# chapr.net
KiCad netlist of a schematic drawn in EAGLE
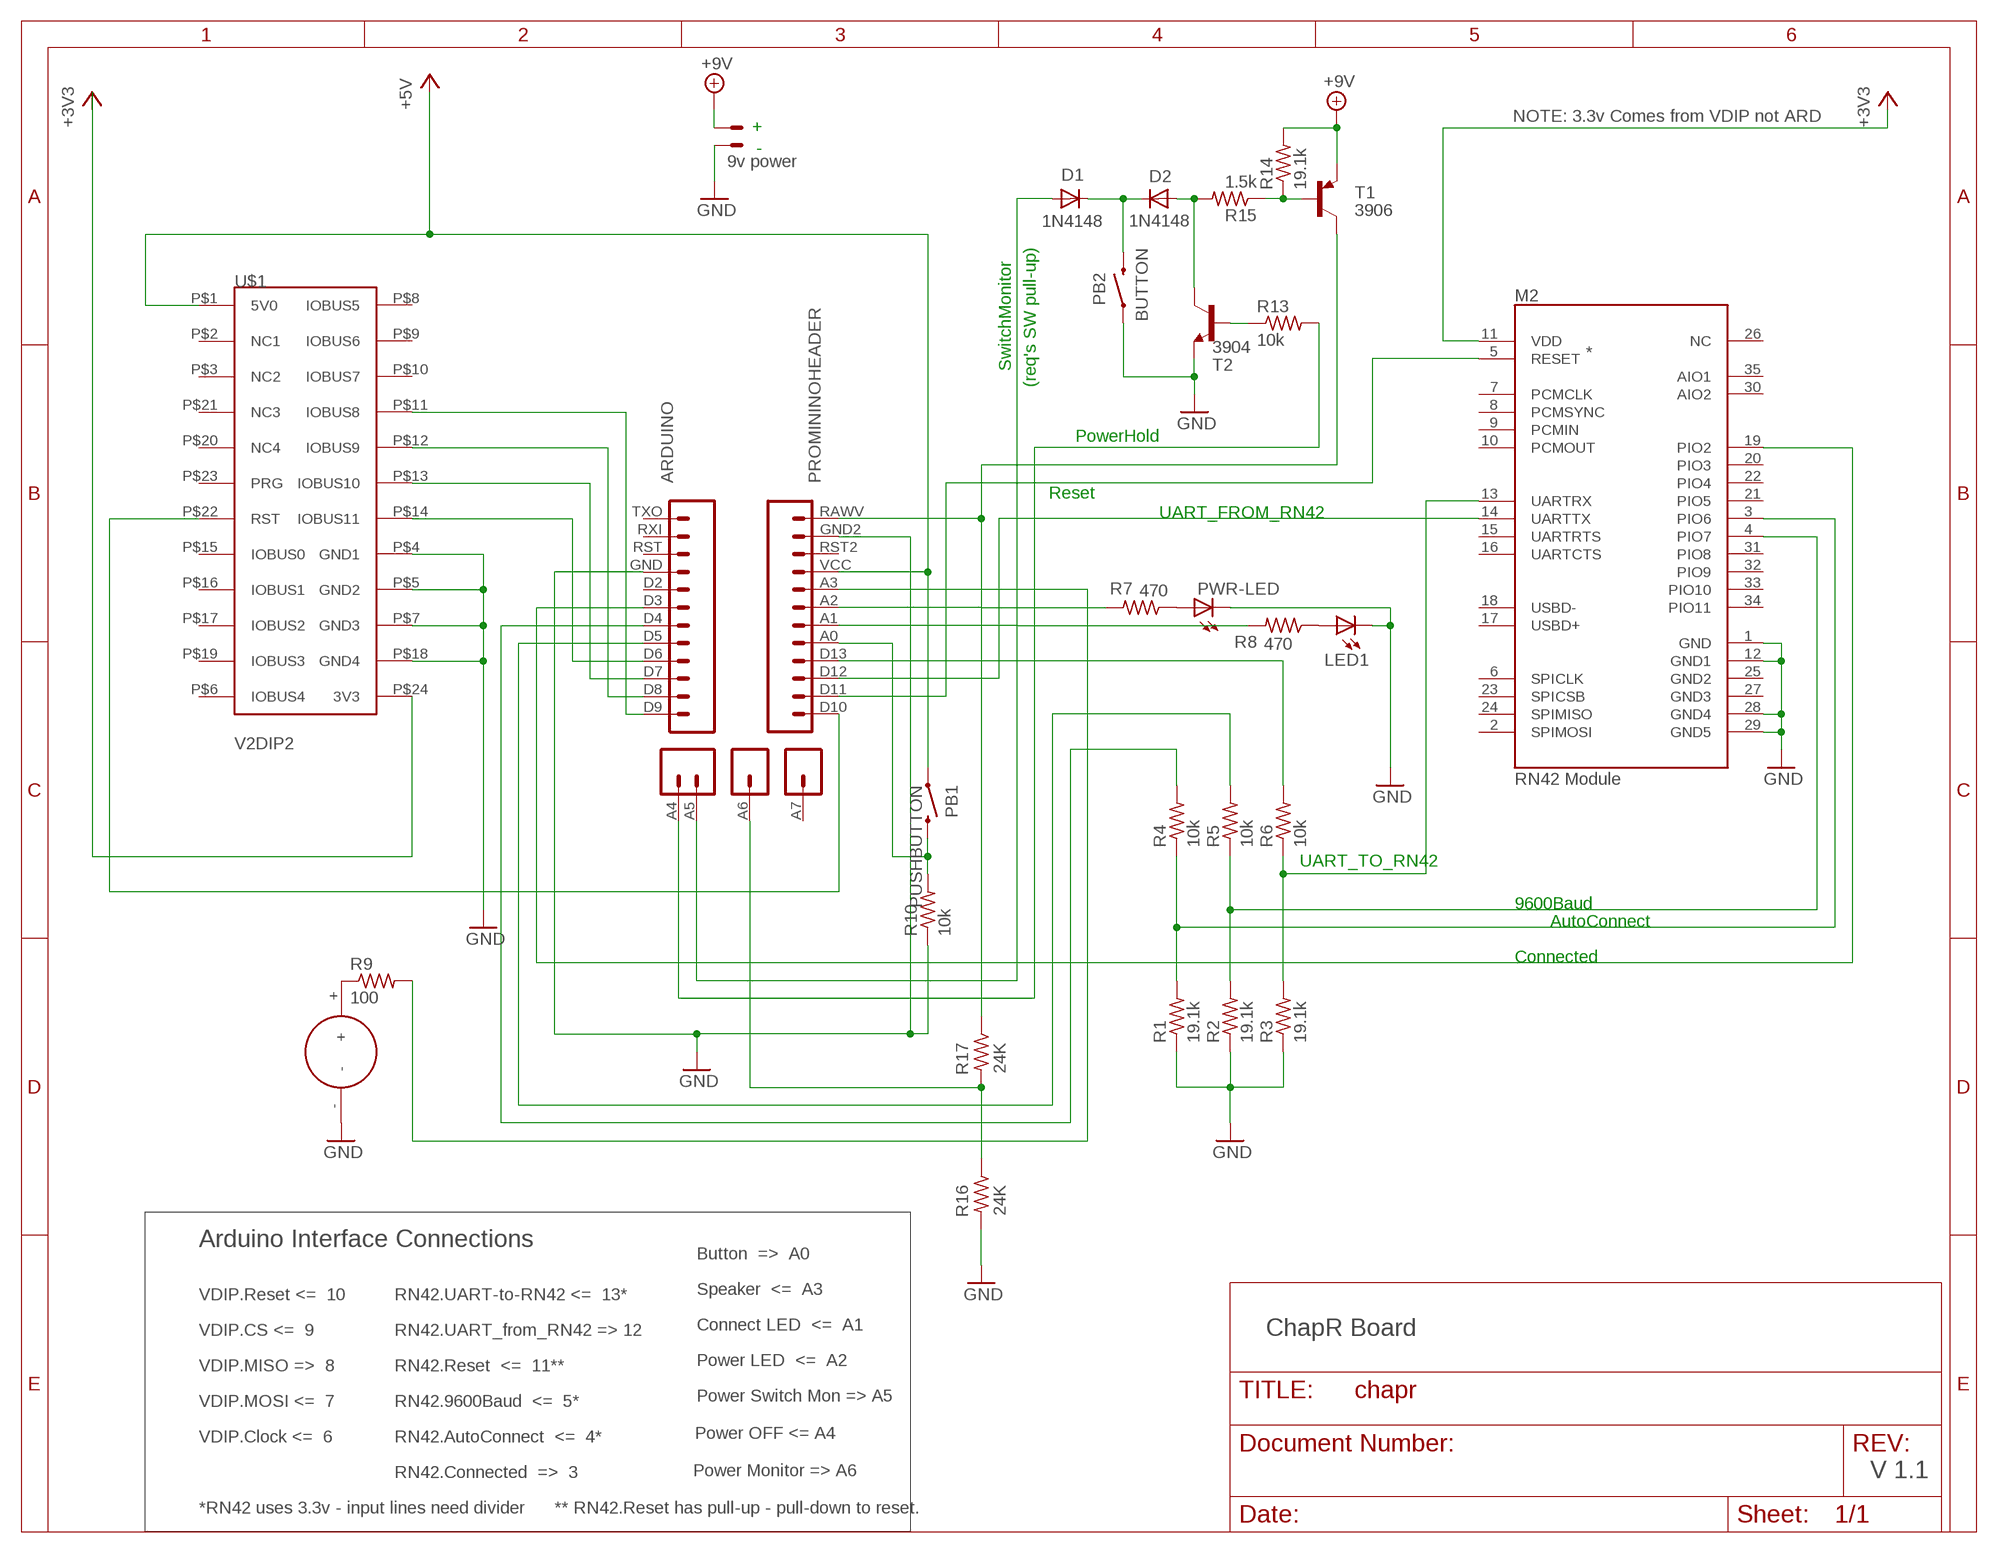
[diagram p0: schematic, sheet 1]

(export (version "E")
  (design (tool "Eeschema 10.0.6"))
  (components
    (comp (ref "-")
      (value "9v power")
      (footprint "eagle-import:22-23-2021")
      (fields (field (name "MF") "MOLEX") (field (name "MPN") "22-23-2021"))
      (libsource (lib "eagle-import") (part "22-23-2021"))
    )
    (comp (ref "ARDUINO")
      (value "PROMININOHEADER")
      (footprint "eagle-import:PROMININOHEADER")
      (libsource (lib "eagle-import") (part "PROMININOHEADER"))
    )
    (comp (ref "D1")
      (value "1N4148")
      (footprint "eagle-import:DO35-7")
      (libsource (lib "eagle-import") (part "1N4148DO35-7"))
    )
    (comp (ref "D2")
      (value "1N4148")
      (footprint "eagle-import:DO35-7")
      (libsource (lib "eagle-import") (part "1N4148DO35-7"))
    )
    (comp (ref "LED1")
      (value "LED3MM")
      (footprint "eagle-import:LED3MM")
      (libsource (lib "eagle-import") (part "LED3MM"))
    )
    (comp (ref "M2")
      (value "RN42 Module")
      (footprint "eagle-import:RN41")
      (libsource (lib "eagle-import") (part "BLUETOOTH-RN41{dblquote}"))
    )
    (comp (ref "PB1")
      (value "PUSHBUTTON")
      (footprint "eagle-import:2-PIN-PUSHBUTTON")
      (libsource (lib "eagle-import") (part "PUSHBUTTON"))
    )
    (comp (ref "PB2")
      (value "BUTTON")
      (footprint "eagle-import:2-PIN-PUSHBUTTON")
      (libsource (lib "eagle-import") (part "PUSHBUTTON"))
    )
    (comp (ref "PWR-LED")
      (value "LED3MM")
      (footprint "eagle-import:LED3MM")
      (libsource (lib "eagle-import") (part "LED3MM"))
    )
    (comp (ref "R1")
      (value "19.1k")
      (footprint "eagle-import:0207_10")
      (libsource (lib "eagle-import") (part "R-US_0207/10"))
    )
    (comp (ref "R2")
      (value "19.1k")
      (footprint "eagle-import:0207_10")
      (libsource (lib "eagle-import") (part "R-US_0207/10"))
    )
    (comp (ref "R3")
      (value "19.1k")
      (footprint "eagle-import:0207_10")
      (libsource (lib "eagle-import") (part "R-US_0207/10"))
    )
    (comp (ref "R4")
      (value "10k")
      (footprint "eagle-import:0207_10")
      (libsource (lib "eagle-import") (part "R-US_0207/10"))
    )
    (comp (ref "R5")
      (value "10k")
      (footprint "eagle-import:0207_10")
      (libsource (lib "eagle-import") (part "R-US_0207/10"))
    )
    (comp (ref "R6")
      (value "10k")
      (footprint "eagle-import:0207_10")
      (libsource (lib "eagle-import") (part "R-US_0207/10"))
    )
    (comp (ref "R7")
      (value "470")
      (footprint "eagle-import:0207_10")
      (libsource (lib "eagle-import") (part "R-US_0207/10"))
    )
    (comp (ref "R8")
      (value "470")
      (footprint "eagle-import:0207_10")
      (libsource (lib "eagle-import") (part "R-US_0207/10"))
    )
    (comp (ref "R9")
      (value "100")
      (footprint "eagle-import:0207_10")
      (libsource (lib "eagle-import") (part "R-US_0207/10"))
    )
    (comp (ref "R10")
      (value "10k")
      (footprint "eagle-import:0207_10")
      (libsource (lib "eagle-import") (part "R-US_0207/10"))
    )
    (comp (ref "R13")
      (value "10k")
      (footprint "eagle-import:0207_10")
      (libsource (lib "eagle-import") (part "R-US_0207/10"))
    )
    (comp (ref "R14")
      (value "19.1k")
      (footprint "eagle-import:0207_10")
      (libsource (lib "eagle-import") (part "R-US_0207/10"))
    )
    (comp (ref "R15")
      (value "1.5k")
      (footprint "eagle-import:0207_10")
      (libsource (lib "eagle-import") (part "R-US_0207/10"))
    )
    (comp (ref "R16")
      (value "24K")
      (footprint "eagle-import:0207_10")
      (libsource (lib "eagle-import") (part "R-US_0207/10"))
    )
    (comp (ref "R17")
      (value "24K")
      (footprint "eagle-import:0207_10")
      (libsource (lib "eagle-import") (part "R-US_0207/10"))
    )
    (comp (ref "T1")
      (value "3906")
      (footprint "eagle-import:TO92-EBC")
      (libsource (lib "eagle-import") (part "-PNP-TO92-EBC"))
    )
    (comp (ref "T2")
      (value "3904")
      (footprint "eagle-import:TO92-EBC")
      (libsource (lib "eagle-import") (part "-NPN-TO92-EBC"))
    )
    (comp (ref "U$1")
      (value "V2DIP2")
      (footprint "eagle-import:V2DIP2")
      (libsource (lib "eagle-import") (part "V2DIP2"))
    )
    (comp (ref "U$2")
      (value "SPEAKER")
      (footprint "eagle-import:SPEAKER")
      (libsource (lib "eagle-import") (part "SPEAKER"))
    )
  )
  (nets
    (net (code "1") (name "+3V3") (class "Default")
      (node (ref "M2") (pin "11") (pinfunction "VDD_11") (pintype "bidirectional"))
      (node (ref "U$1") (pin "P$24") (pinfunction "3V3_P$24") (pintype "bidirectional"))
    )
    (net (code "2") (name "+5V") (class "Default")
      (node (ref "ARDUINO") (pin "VCC") (pinfunction "VCC_VCC") (pintype "passive"))
      (node (ref "PB1") (pin "P$1") (pinfunction "1_P$1") (pintype "passive"))
      (node (ref "U$1") (pin "P$1") (pinfunction "5V0_P$1") (pintype "bidirectional"))
    )
    (net (code "3") (name "+9V") (class "Default")
      (node (ref "-") (pin "2") (pinfunction "S_2") (pintype "passive"))
      (node (ref "R14") (pin "2") (pinfunction "2_2") (pintype "passive"))
      (node (ref "T1") (pin "E") (pinfunction "E_E") (pintype "passive"))
    )
    (net (code "4") (name "GND") (class "Default")
      (node (ref "-") (pin "1") (pinfunction "S_1") (pintype "passive"))
      (node (ref "ARDUINO") (pin "GND") (pinfunction "GND_GND") (pintype "passive"))
      (node (ref "ARDUINO") (pin "GND2") (pinfunction "GND2_GND2") (pintype "passive"))
      (node (ref "LED1") (pin "K") (pinfunction "C_K") (pintype "passive"))
      (node (ref "M2") (pin "1") (pinfunction "GND_1") (pintype "bidirectional"))
      (node (ref "M2") (pin "12") (pinfunction "GND1_12") (pintype "bidirectional"))
      (node (ref "M2") (pin "28") (pinfunction "GND4_28") (pintype "bidirectional"))
      (node (ref "M2") (pin "29") (pinfunction "GND5_29") (pintype "bidirectional"))
      (node (ref "PB2") (pin "P$1") (pinfunction "1_P$1") (pintype "passive"))
      (node (ref "PWR-LED") (pin "K") (pinfunction "C_K") (pintype "passive"))
      (node (ref "R1") (pin "1") (pinfunction "1_1") (pintype "passive"))
      (node (ref "R10") (pin "1") (pinfunction "1_1") (pintype "passive"))
      (node (ref "R16") (pin "2") (pinfunction "2_2") (pintype "passive"))
      (node (ref "R2") (pin "1") (pinfunction "1_1") (pintype "passive"))
      (node (ref "R3") (pin "1") (pinfunction "1_1") (pintype "passive"))
      (node (ref "T2") (pin "E") (pinfunction "E_E") (pintype "passive"))
      (node (ref "U$1") (pin "P$18") (pinfunction "GND4_P$18") (pintype "bidirectional"))
      (node (ref "U$1") (pin "P$4") (pinfunction "GND1_P$4") (pintype "bidirectional"))
      (node (ref "U$1") (pin "P$5") (pinfunction "GND2_P$5") (pintype "bidirectional"))
      (node (ref "U$1") (pin "P$7") (pinfunction "GND3_P$7") (pintype "bidirectional"))
      (node (ref "U$2") (pin "-") (pinfunction "-_-") (pintype "bidirectional"))
    )
    (net (code "5") (name "Net-(ARDUINO-PadA1)") (class "Default")
      (node (ref "ARDUINO") (pin "A1") (pinfunction "A1_A1") (pintype "passive"))
      (node (ref "R8") (pin "2") (pinfunction "2_2") (pintype "passive"))
    )
    (net (code "6") (name "Net-(ARDUINO-PadA2)") (class "Default")
      (node (ref "ARDUINO") (pin "A2") (pinfunction "A2_A2") (pintype "passive"))
      (node (ref "R7") (pin "2") (pinfunction "2_2") (pintype "passive"))
    )
    (net (code "7") (name "Net-(ARDUINO-PadA3)") (class "Default")
      (node (ref "ARDUINO") (pin "A3") (pinfunction "A3_A3") (pintype "passive"))
      (node (ref "R9") (pin "2") (pinfunction "2_2") (pintype "passive"))
    )
    (net (code "8") (name "Net-(ARDUINO-PadA4)") (class "Default")
      (node (ref "ARDUINO") (pin "A4") (pinfunction "A4_A4") (pintype "passive"))
      (node (ref "R13") (pin "2") (pinfunction "2_2") (pintype "passive"))
    )
    (net (code "9") (name "Net-(ARDUINO-PadA5)") (class "Default")
      (node (ref "ARDUINO") (pin "A5") (pinfunction "A5_A5") (pintype "passive"))
      (node (ref "D1") (pin "A") (pinfunction "A_A") (pintype "passive"))
    )
    (net (code "10") (name "Net-(ARDUINO-PadA6)") (class "Default")
      (node (ref "ARDUINO") (pin "A6") (pinfunction "A6_A6") (pintype "passive"))
      (node (ref "R16") (pin "1") (pinfunction "1_1") (pintype "passive"))
      (node (ref "R17") (pin "2") (pinfunction "2_2") (pintype "passive"))
    )
    (net (code "11") (name "Net-(ARDUINO-PadD4)") (class "Default")
      (node (ref "ARDUINO") (pin "D4") (pinfunction "D4_D4") (pintype "passive"))
      (node (ref "R4") (pin "2") (pinfunction "2_2") (pintype "passive"))
    )
    (net (code "12") (name "Net-(ARDUINO-PadD5)") (class "Default")
      (node (ref "ARDUINO") (pin "D5") (pinfunction "D5_D5") (pintype "passive"))
      (node (ref "R5") (pin "2") (pinfunction "2_2") (pintype "passive"))
    )
    (net (code "13") (name "Net-(ARDUINO-PadD13)") (class "Default")
      (node (ref "ARDUINO") (pin "D13") (pinfunction "D13_D13") (pintype "passive"))
      (node (ref "R6") (pin "2") (pinfunction "2_2") (pintype "passive"))
    )
    (net (code "14") (name "Net-(ARDUINO-PadRAWV)") (class "Default")
      (node (ref "ARDUINO") (pin "RAWV") (pinfunction "RAWV_RAWV") (pintype "passive"))
      (node (ref "R17") (pin "1") (pinfunction "1_1") (pintype "passive"))
      (node (ref "T1") (pin "C") (pinfunction "C_C") (pintype "passive"))
    )
    (net (code "15") (name "Net-(D2-PadA)") (class "Default")
      (node (ref "D2") (pin "A") (pinfunction "A_A") (pintype "passive"))
      (node (ref "R15") (pin "2") (pinfunction "2_2") (pintype "passive"))
      (node (ref "T2") (pin "C") (pinfunction "C_C") (pintype "passive"))
    )
    (net (code "16") (name "Net-(LED1-PadA)") (class "Default")
      (node (ref "LED1") (pin "A") (pinfunction "A_A") (pintype "passive"))
      (node (ref "R8") (pin "1") (pinfunction "1_1") (pintype "passive"))
    )
    (net (code "17") (name "Net-(M2-PIO2)") (class "Default")
      (node (ref "ARDUINO") (pin "D3") (pinfunction "D3_D3") (pintype "passive"))
      (node (ref "M2") (pin "19") (pinfunction "PIO2_19") (pintype "bidirectional"))
    )
    (net (code "18") (name "Net-(M2-PIO6)") (class "Default")
      (node (ref "M2") (pin "3") (pinfunction "PIO6_3") (pintype "bidirectional"))
      (node (ref "R1") (pin "2") (pinfunction "2_2") (pintype "passive"))
      (node (ref "R4") (pin "1") (pinfunction "1_1") (pintype "passive"))
    )
    (net (code "19") (name "Net-(M2-PIO7)") (class "Default")
      (node (ref "M2") (pin "4") (pinfunction "PIO7_4") (pintype "bidirectional"))
      (node (ref "R2") (pin "2") (pinfunction "2_2") (pintype "passive"))
      (node (ref "R5") (pin "1") (pinfunction "1_1") (pintype "passive"))
    )
    (net (code "20") (name "Net-(M2-RESET)") (class "Default")
      (node (ref "ARDUINO") (pin "D11") (pinfunction "D11_D11") (pintype "passive"))
      (node (ref "M2") (pin "5") (pinfunction "RESET_5") (pintype "bidirectional"))
    )
    (net (code "21") (name "Net-(M2-UARTRX)") (class "Default")
      (node (ref "M2") (pin "13") (pinfunction "UARTRX_13") (pintype "bidirectional"))
      (node (ref "R3") (pin "2") (pinfunction "2_2") (pintype "passive"))
      (node (ref "R6") (pin "1") (pinfunction "1_1") (pintype "passive"))
    )
    (net (code "22") (name "Net-(M2-UARTTX)") (class "Default")
      (node (ref "ARDUINO") (pin "D12") (pinfunction "D12_D12") (pintype "passive"))
      (node (ref "M2") (pin "14") (pinfunction "UARTTX_14") (pintype "bidirectional"))
    )
    (net (code "23") (name "Net-(PB1-2)") (class "Default")
      (node (ref "ARDUINO") (pin "A0") (pinfunction "A0_A0") (pintype "passive"))
      (node (ref "PB1") (pin "P$2") (pinfunction "2_P$2") (pintype "passive"))
      (node (ref "R10") (pin "2") (pinfunction "2_2") (pintype "passive"))
    )
    (net (code "24") (name "Net-(PB2-2)") (class "Default")
      (node (ref "D1") (pin "C") (pinfunction "C_C") (pintype "passive"))
      (node (ref "D2") (pin "C") (pinfunction "C_C") (pintype "passive"))
      (node (ref "PB2") (pin "P$2") (pinfunction "2_P$2") (pintype "passive"))
    )
    (net (code "25") (name "Net-(PWR-LED-PadA)") (class "Default")
      (node (ref "PWR-LED") (pin "A") (pinfunction "A_A") (pintype "passive"))
      (node (ref "R7") (pin "1") (pinfunction "1_1") (pintype "passive"))
    )
    (net (code "26") (name "Net-(R9-Pad1)") (class "Default")
      (node (ref "R9") (pin "1") (pinfunction "1_1") (pintype "passive"))
      (node (ref "U$2") (pin "+") (pinfunction "+_+") (pintype "bidirectional"))
    )
    (net (code "27") (name "Net-(R13-Pad1)") (class "Default")
      (node (ref "R13") (pin "1") (pinfunction "1_1") (pintype "passive"))
      (node (ref "T2") (pin "B") (pinfunction "B_B") (pintype "passive"))
    )
    (net (code "28") (name "Net-(R14-Pad1)") (class "Default")
      (node (ref "R14") (pin "1") (pinfunction "1_1") (pintype "passive"))
      (node (ref "R15") (pin "1") (pinfunction "1_1") (pintype "passive"))
      (node (ref "T1") (pin "B") (pinfunction "B_B") (pintype "passive"))
    )
    (net (code "29") (name "Net-(U$1-IOBUS8)") (class "Default")
      (node (ref "ARDUINO") (pin "D9") (pinfunction "D9_D9") (pintype "passive"))
      (node (ref "U$1") (pin "P$11") (pinfunction "IOBUS8_P$11") (pintype "bidirectional"))
    )
    (net (code "30") (name "Net-(U$1-IOBUS9)") (class "Default")
      (node (ref "ARDUINO") (pin "D8") (pinfunction "D8_D8") (pintype "passive"))
      (node (ref "U$1") (pin "P$12") (pinfunction "IOBUS9_P$12") (pintype "bidirectional"))
    )
    (net (code "31") (name "Net-(U$1-IOBUS10)") (class "Default")
      (node (ref "ARDUINO") (pin "D7") (pinfunction "D7_D7") (pintype "passive"))
      (node (ref "U$1") (pin "P$13") (pinfunction "IOBUS10_P$13") (pintype "bidirectional"))
    )
    (net (code "32") (name "Net-(U$1-IOBUS11)") (class "Default")
      (node (ref "ARDUINO") (pin "D6") (pinfunction "D6_D6") (pintype "passive"))
      (node (ref "U$1") (pin "P$14") (pinfunction "IOBUS11_P$14") (pintype "bidirectional"))
    )
    (net (code "33") (name "Net-(U$1-RST)") (class "Default")
      (node (ref "ARDUINO") (pin "D10") (pinfunction "D10_D10") (pintype "passive"))
      (node (ref "U$1") (pin "P$22") (pinfunction "RST_P$22") (pintype "bidirectional"))
    )
    (net (code "34") (name "unconnected-(ARDUINO-PadA7)") (class "Default")
      (node (ref "ARDUINO") (pin "A7") (pinfunction "A7_A7") (pintype "passive"))
    )
    (net (code "35") (name "unconnected-(ARDUINO-PadD2)") (class "Default")
      (node (ref "ARDUINO") (pin "D2") (pinfunction "D2_D2") (pintype "passive"))
    )
    (net (code "36") (name "unconnected-(ARDUINO-PadRST)") (class "Default")
      (node (ref "ARDUINO") (pin "RST") (pinfunction "RST_RST") (pintype "passive"))
    )
    (net (code "37") (name "unconnected-(ARDUINO-PadRST2)") (class "Default")
      (node (ref "ARDUINO") (pin "RST2") (pinfunction "RST2_RST2") (pintype "passive"))
    )
    (net (code "38") (name "unconnected-(ARDUINO-PadRXI)") (class "Default")
      (node (ref "ARDUINO") (pin "RXI") (pinfunction "RXI_RXI") (pintype "passive"))
    )
    (net (code "39") (name "unconnected-(ARDUINO-PadTXO)") (class "Default")
      (node (ref "ARDUINO") (pin "TXO") (pinfunction "TXO_TXO") (pintype "passive"))
    )
    (net (code "40") (name "unconnected-(M2-AIO1-Pad35)") (class "Default")
      (node (ref "M2") (pin "35") (pinfunction "AIO1_35") (pintype "bidirectional"))
    )
    (net (code "41") (name "unconnected-(M2-AIO2-Pad30)") (class "Default")
      (node (ref "M2") (pin "30") (pinfunction "AIO2_30") (pintype "bidirectional"))
    )
    (net (code "42") (name "unconnected-(M2-GND2-Pad25)") (class "Default")
      (node (ref "M2") (pin "25") (pinfunction "GND2_25") (pintype "bidirectional"))
    )
    (net (code "43") (name "unconnected-(M2-GND3-Pad27)") (class "Default")
      (node (ref "M2") (pin "27") (pinfunction "GND3_27") (pintype "bidirectional"))
    )
    (net (code "44") (name "unconnected-(M2-NC-Pad26)") (class "Default")
      (node (ref "M2") (pin "26") (pinfunction "NC_26") (pintype "bidirectional"))
    )
    (net (code "45") (name "unconnected-(M2-PCMCLK-Pad7)") (class "Default")
      (node (ref "M2") (pin "7") (pinfunction "PCMCLK_7") (pintype "bidirectional"))
    )
    (net (code "46") (name "unconnected-(M2-PCMIN-Pad9)") (class "Default")
      (node (ref "M2") (pin "9") (pinfunction "PCMIN_9") (pintype "bidirectional"))
    )
    (net (code "47") (name "unconnected-(M2-PCMOUT-Pad10)") (class "Default")
      (node (ref "M2") (pin "10") (pinfunction "PCMOUT_10") (pintype "bidirectional"))
    )
    (net (code "48") (name "unconnected-(M2-PCMSYNC-Pad8)") (class "Default")
      (node (ref "M2") (pin "8") (pinfunction "PCMSYNC_8") (pintype "bidirectional"))
    )
    (net (code "49") (name "unconnected-(M2-PIO3-Pad20)") (class "Default")
      (node (ref "M2") (pin "20") (pinfunction "PIO3_20") (pintype "bidirectional"))
    )
    (net (code "50") (name "unconnected-(M2-PIO4-Pad22)") (class "Default")
      (node (ref "M2") (pin "22") (pinfunction "PIO4_22") (pintype "bidirectional"))
    )
    (net (code "51") (name "unconnected-(M2-PIO5-Pad21)") (class "Default")
      (node (ref "M2") (pin "21") (pinfunction "PIO5_21") (pintype "bidirectional"))
    )
    (net (code "52") (name "unconnected-(M2-PIO8-Pad31)") (class "Default")
      (node (ref "M2") (pin "31") (pinfunction "PIO8_31") (pintype "bidirectional"))
    )
    (net (code "53") (name "unconnected-(M2-PIO9-Pad32)") (class "Default")
      (node (ref "M2") (pin "32") (pinfunction "PIO9_32") (pintype "bidirectional"))
    )
    (net (code "54") (name "unconnected-(M2-PIO10-Pad33)") (class "Default")
      (node (ref "M2") (pin "33") (pinfunction "PIO10_33") (pintype "bidirectional"))
    )
    (net (code "55") (name "unconnected-(M2-PIO11-Pad34)") (class "Default")
      (node (ref "M2") (pin "34") (pinfunction "PIO11_34") (pintype "bidirectional"))
    )
    (net (code "56") (name "unconnected-(M2-SPICLK-Pad6)") (class "Default")
      (node (ref "M2") (pin "6") (pinfunction "SPICLK_6") (pintype "bidirectional"))
    )
    (net (code "57") (name "unconnected-(M2-SPICSB-Pad23)") (class "Default")
      (node (ref "M2") (pin "23") (pinfunction "SPICSB_23") (pintype "bidirectional"))
    )
    (net (code "58") (name "unconnected-(M2-SPIMISO-Pad24)") (class "Default")
      (node (ref "M2") (pin "24") (pinfunction "SPIMISO_24") (pintype "bidirectional"))
    )
    (net (code "59") (name "unconnected-(M2-SPIMOSI-Pad2)") (class "Default")
      (node (ref "M2") (pin "2") (pinfunction "SPIMOSI_2") (pintype "bidirectional"))
    )
    (net (code "60") (name "unconnected-(M2-UARTCTS-Pad16)") (class "Default")
      (node (ref "M2") (pin "16") (pinfunction "UARTCTS_16") (pintype "bidirectional"))
    )
    (net (code "61") (name "unconnected-(M2-UARTRTS-Pad15)") (class "Default")
      (node (ref "M2") (pin "15") (pinfunction "UARTRTS_15") (pintype "bidirectional"))
    )
    (net (code "62") (name "unconnected-(M2-USBD+-Pad17)") (class "Default")
      (node (ref "M2") (pin "17") (pinfunction "USBD+_17") (pintype "bidirectional"))
    )
    (net (code "63") (name "unconnected-(M2-USBD--Pad18)") (class "Default")
      (node (ref "M2") (pin "18") (pinfunction "USBD-_18") (pintype "bidirectional"))
    )
    (net (code "64") (name "unconnected-(U$1-IOBUS0-PadP$15)") (class "Default")
      (node (ref "U$1") (pin "P$15") (pinfunction "IOBUS0_P$15") (pintype "bidirectional"))
    )
    (net (code "65") (name "unconnected-(U$1-IOBUS1-PadP$16)") (class "Default")
      (node (ref "U$1") (pin "P$16") (pinfunction "IOBUS1_P$16") (pintype "bidirectional"))
    )
    (net (code "66") (name "unconnected-(U$1-IOBUS2-PadP$17)") (class "Default")
      (node (ref "U$1") (pin "P$17") (pinfunction "IOBUS2_P$17") (pintype "bidirectional"))
    )
    (net (code "67") (name "unconnected-(U$1-IOBUS3-PadP$19)") (class "Default")
      (node (ref "U$1") (pin "P$19") (pinfunction "IOBUS3_P$19") (pintype "bidirectional"))
    )
    (net (code "68") (name "unconnected-(U$1-IOBUS4-PadP$6)") (class "Default")
      (node (ref "U$1") (pin "P$6") (pinfunction "IOBUS4_P$6") (pintype "bidirectional"))
    )
    (net (code "69") (name "unconnected-(U$1-IOBUS5-PadP$8)") (class "Default")
      (node (ref "U$1") (pin "P$8") (pinfunction "IOBUS5_P$8") (pintype "bidirectional"))
    )
    (net (code "70") (name "unconnected-(U$1-IOBUS6-PadP$9)") (class "Default")
      (node (ref "U$1") (pin "P$9") (pinfunction "IOBUS6_P$9") (pintype "bidirectional"))
    )
    (net (code "71") (name "unconnected-(U$1-IOBUS7-PadP$10)") (class "Default")
      (node (ref "U$1") (pin "P$10") (pinfunction "IOBUS7_P$10") (pintype "bidirectional"))
    )
    (net (code "72") (name "unconnected-(U$1-NC1-PadP$2)") (class "Default")
      (node (ref "U$1") (pin "P$2") (pinfunction "NC1_P$2") (pintype "bidirectional"))
    )
    (net (code "73") (name "unconnected-(U$1-NC2-PadP$3)") (class "Default")
      (node (ref "U$1") (pin "P$3") (pinfunction "NC2_P$3") (pintype "bidirectional"))
    )
    (net (code "74") (name "unconnected-(U$1-NC3-PadP$21)") (class "Default")
      (node (ref "U$1") (pin "P$21") (pinfunction "NC3_P$21") (pintype "bidirectional"))
    )
    (net (code "75") (name "unconnected-(U$1-NC4-PadP$20)") (class "Default")
      (node (ref "U$1") (pin "P$20") (pinfunction "NC4_P$20") (pintype "bidirectional"))
    )
    (net (code "76") (name "unconnected-(U$1-PRG-PadP$23)") (class "Default")
      (node (ref "U$1") (pin "P$23") (pinfunction "PRG_P$23") (pintype "bidirectional"))
    )
  )
)
